# 2_classyTKL_MXHS_matrix.net
KiCad netlist of a schematic drawn in Altium Designer
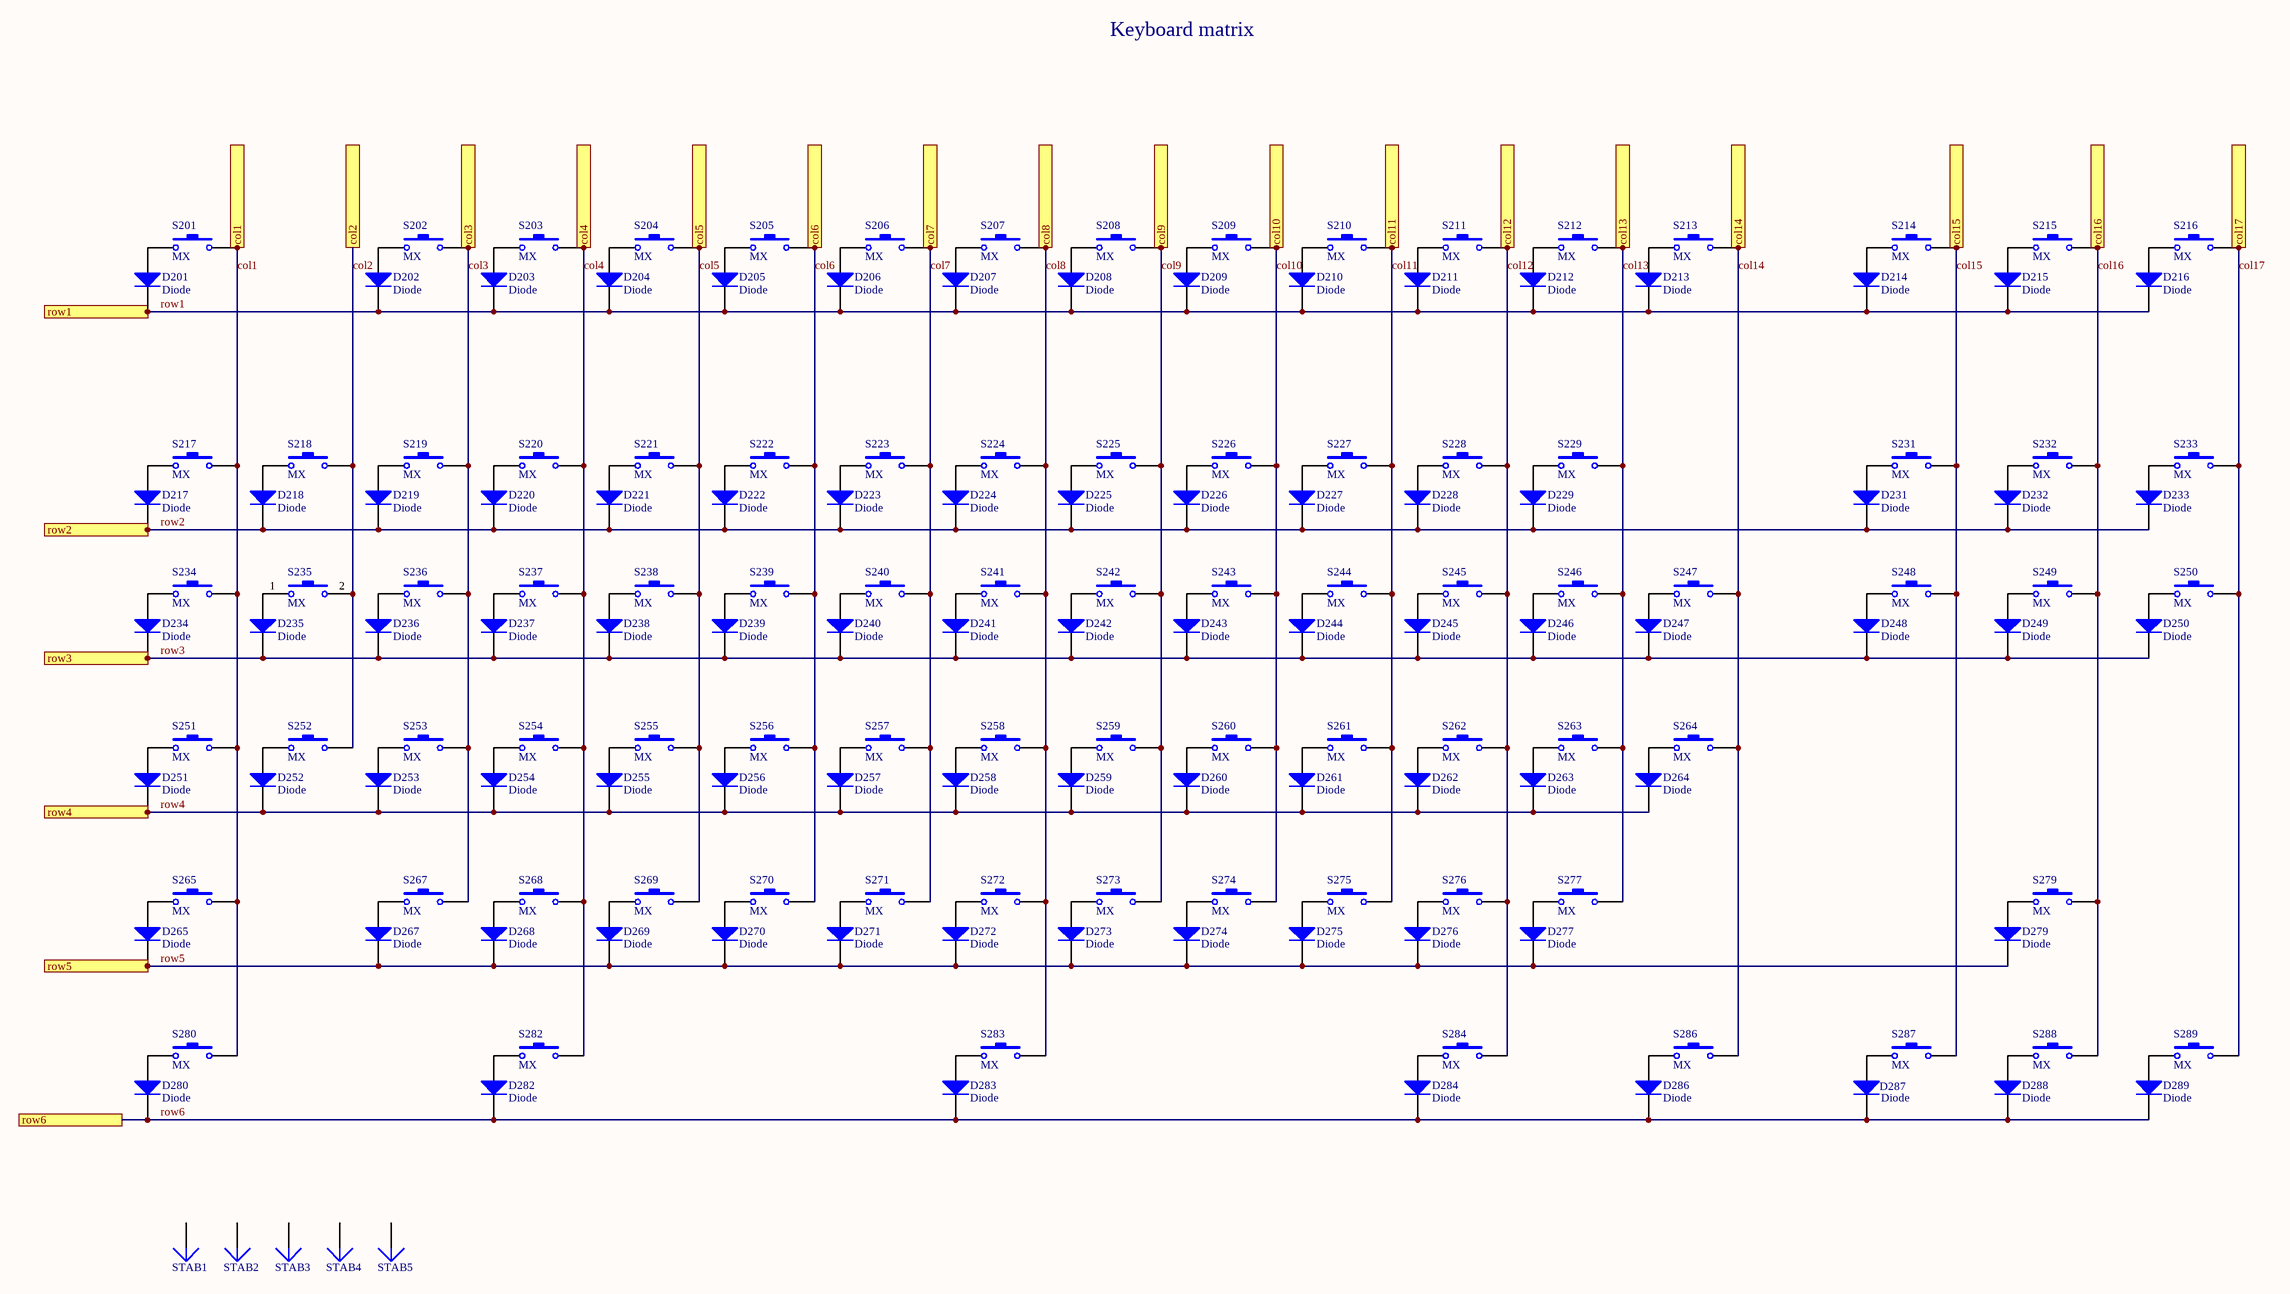
[diagram p0: 2_classyTKL_MXHS_matrix.SchDoc]

(export (version "E")
  (design (tool "Eeschema 10.0.6"))
  (components
    (comp (ref "D201")
      (value "Diode")
      (footprint "SOD-123")
      (description "Default Diode")
      (fields (field (name "LCSC PART #") "C81598") (field (name "MRF.PART") "1N4148W"))
      (libsource (lib "Miscellaneous Devices") (part "Diode"))
    )
    (comp (ref "D202")
      (value "Diode")
      (footprint "SOD-123")
      (description "Default Diode")
      (fields (field (name "LCSC PART #") "C81598") (field (name "MRF.PART") "1N4148W"))
      (libsource (lib "Miscellaneous Devices") (part "Diode"))
    )
    (comp (ref "D203")
      (value "Diode")
      (footprint "SOD-123")
      (description "Default Diode")
      (fields (field (name "LCSC PART #") "C81598") (field (name "MRF.PART") "1N4148W"))
      (libsource (lib "Miscellaneous Devices") (part "Diode"))
    )
    (comp (ref "D204")
      (value "Diode")
      (footprint "SOD-123")
      (description "Default Diode")
      (fields (field (name "LCSC PART #") "C81598") (field (name "MRF.PART") "1N4148W"))
      (libsource (lib "Miscellaneous Devices") (part "Diode"))
    )
    (comp (ref "D205")
      (value "Diode")
      (footprint "SOD-123")
      (description "Default Diode")
      (fields (field (name "LCSC PART #") "C81598") (field (name "MRF.PART") "1N4148W"))
      (libsource (lib "Miscellaneous Devices") (part "Diode"))
    )
    (comp (ref "D206")
      (value "Diode")
      (footprint "SOD-123")
      (description "Default Diode")
      (fields (field (name "LCSC PART #") "C81598") (field (name "MRF.PART") "1N4148W"))
      (libsource (lib "Miscellaneous Devices") (part "Diode"))
    )
    (comp (ref "D207")
      (value "Diode")
      (footprint "SOD-123")
      (description "Default Diode")
      (fields (field (name "LCSC PART #") "C81598") (field (name "MRF.PART") "1N4148W"))
      (libsource (lib "Miscellaneous Devices") (part "Diode"))
    )
    (comp (ref "D208")
      (value "Diode")
      (footprint "SOD-123")
      (description "Default Diode")
      (fields (field (name "LCSC PART #") "C81598") (field (name "MRF.PART") "1N4148W"))
      (libsource (lib "Miscellaneous Devices") (part "Diode"))
    )
    (comp (ref "D209")
      (value "Diode")
      (footprint "SOD-123")
      (description "Default Diode")
      (fields (field (name "LCSC PART #") "C81598") (field (name "MRF.PART") "1N4148W"))
      (libsource (lib "Miscellaneous Devices") (part "Diode"))
    )
    (comp (ref "D210")
      (value "Diode")
      (footprint "SOD-123")
      (description "Default Diode")
      (fields (field (name "LCSC PART #") "C81598") (field (name "MRF.PART") "1N4148W"))
      (libsource (lib "Miscellaneous Devices") (part "Diode"))
    )
    (comp (ref "D211")
      (value "Diode")
      (footprint "SOD-123")
      (description "Default Diode")
      (fields (field (name "LCSC PART #") "C81598") (field (name "MRF.PART") "1N4148W"))
      (libsource (lib "Miscellaneous Devices") (part "Diode"))
    )
    (comp (ref "D212")
      (value "Diode")
      (footprint "SOD-123")
      (description "Default Diode")
      (fields (field (name "LCSC PART #") "C81598") (field (name "MRF.PART") "1N4148W"))
      (libsource (lib "Miscellaneous Devices") (part "Diode"))
    )
    (comp (ref "D213")
      (value "Diode")
      (footprint "SOD-123")
      (description "Default Diode")
      (fields (field (name "LCSC PART #") "C81598") (field (name "MRF.PART") "1N4148W"))
      (libsource (lib "Miscellaneous Devices") (part "Diode"))
    )
    (comp (ref "D214")
      (value "Diode")
      (footprint "SOD-123")
      (description "Default Diode")
      (fields (field (name "LCSC PART #") "C81598") (field (name "MRF.PART") "1N4148W"))
      (libsource (lib "Miscellaneous Devices") (part "Diode"))
    )
    (comp (ref "D215")
      (value "Diode")
      (footprint "SOD-123")
      (description "Default Diode")
      (fields (field (name "LCSC PART #") "C81598") (field (name "MRF.PART") "1N4148W"))
      (libsource (lib "Miscellaneous Devices") (part "Diode"))
    )
    (comp (ref "D216")
      (value "Diode")
      (footprint "SOD-123")
      (description "Default Diode")
      (fields (field (name "LCSC PART #") "C81598") (field (name "MRF.PART") "1N4148W"))
      (libsource (lib "Miscellaneous Devices") (part "Diode"))
    )
    (comp (ref "D217")
      (value "Diode")
      (footprint "SOD-123")
      (description "Default Diode")
      (fields (field (name "LCSC PART #") "C81598") (field (name "MRF.PART") "1N4148W"))
      (libsource (lib "Miscellaneous Devices") (part "Diode"))
    )
    (comp (ref "D218")
      (value "Diode")
      (footprint "SOD-123")
      (description "Default Diode")
      (fields (field (name "LCSC PART #") "C81598") (field (name "MRF.PART") "1N4148W"))
      (libsource (lib "Miscellaneous Devices") (part "Diode"))
    )
    (comp (ref "D219")
      (value "Diode")
      (footprint "SOD-123")
      (description "Default Diode")
      (fields (field (name "LCSC PART #") "C81598") (field (name "MRF.PART") "1N4148W"))
      (libsource (lib "Miscellaneous Devices") (part "Diode"))
    )
    (comp (ref "D220")
      (value "Diode")
      (footprint "SOD-123")
      (description "Default Diode")
      (fields (field (name "LCSC PART #") "C81598") (field (name "MRF.PART") "1N4148W"))
      (libsource (lib "Miscellaneous Devices") (part "Diode"))
    )
    (comp (ref "D221")
      (value "Diode")
      (footprint "SOD-123")
      (description "Default Diode")
      (fields (field (name "LCSC PART #") "C81598") (field (name "MRF.PART") "1N4148W"))
      (libsource (lib "Miscellaneous Devices") (part "Diode"))
    )
    (comp (ref "D222")
      (value "Diode")
      (footprint "SOD-123")
      (description "Default Diode")
      (fields (field (name "LCSC PART #") "C81598") (field (name "MRF.PART") "1N4148W"))
      (libsource (lib "Miscellaneous Devices") (part "Diode"))
    )
    (comp (ref "D223")
      (value "Diode")
      (footprint "SOD-123")
      (description "Default Diode")
      (fields (field (name "LCSC PART #") "C81598") (field (name "MRF.PART") "1N4148W"))
      (libsource (lib "Miscellaneous Devices") (part "Diode"))
    )
    (comp (ref "D224")
      (value "Diode")
      (footprint "SOD-123")
      (description "Default Diode")
      (fields (field (name "LCSC PART #") "C81598") (field (name "MRF.PART") "1N4148W"))
      (libsource (lib "Miscellaneous Devices") (part "Diode"))
    )
    (comp (ref "D225")
      (value "Diode")
      (footprint "SOD-123")
      (description "Default Diode")
      (fields (field (name "LCSC PART #") "C81598") (field (name "MRF.PART") "1N4148W"))
      (libsource (lib "Miscellaneous Devices") (part "Diode"))
    )
    (comp (ref "D226")
      (value "Diode")
      (footprint "SOD-123")
      (description "Default Diode")
      (fields (field (name "LCSC PART #") "C81598") (field (name "MRF.PART") "1N4148W"))
      (libsource (lib "Miscellaneous Devices") (part "Diode"))
    )
    (comp (ref "D227")
      (value "Diode")
      (footprint "SOD-123")
      (description "Default Diode")
      (fields (field (name "LCSC PART #") "C81598") (field (name "MRF.PART") "1N4148W"))
      (libsource (lib "Miscellaneous Devices") (part "Diode"))
    )
    (comp (ref "D228")
      (value "Diode")
      (footprint "SOD-123")
      (description "Default Diode")
      (fields (field (name "LCSC PART #") "C81598") (field (name "MRF.PART") "1N4148W"))
      (libsource (lib "Miscellaneous Devices") (part "Diode"))
    )
    (comp (ref "D229")
      (value "Diode")
      (footprint "SOD-123")
      (description "Default Diode")
      (fields (field (name "LCSC PART #") "C81598") (field (name "MRF.PART") "1N4148W"))
      (libsource (lib "Miscellaneous Devices") (part "Diode"))
    )
    (comp (ref "D231")
      (value "Diode")
      (footprint "SOD-123")
      (description "Default Diode")
      (fields (field (name "LCSC PART #") "C81598") (field (name "MRF.PART") "1N4148W"))
      (libsource (lib "Miscellaneous Devices") (part "Diode"))
    )
    (comp (ref "D232")
      (value "Diode")
      (footprint "SOD-123")
      (description "Default Diode")
      (fields (field (name "LCSC PART #") "C81598") (field (name "MRF.PART") "1N4148W"))
      (libsource (lib "Miscellaneous Devices") (part "Diode"))
    )
    (comp (ref "D233")
      (value "Diode")
      (footprint "SOD-123")
      (description "Default Diode")
      (fields (field (name "LCSC PART #") "C81598") (field (name "MRF.PART") "1N4148W"))
      (libsource (lib "Miscellaneous Devices") (part "Diode"))
    )
    (comp (ref "D234")
      (value "Diode")
      (footprint "SOD-123")
      (description "Default Diode")
      (fields (field (name "LCSC PART #") "C81598") (field (name "MRF.PART") "1N4148W"))
      (libsource (lib "Miscellaneous Devices") (part "Diode"))
    )
    (comp (ref "D235")
      (value "Diode")
      (footprint "SOD-123")
      (description "Default Diode")
      (fields (field (name "LCSC PART #") "C81598") (field (name "MRF.PART") "1N4148W"))
      (libsource (lib "Miscellaneous Devices") (part "Diode"))
    )
    (comp (ref "D236")
      (value "Diode")
      (footprint "SOD-123")
      (description "Default Diode")
      (fields (field (name "LCSC PART #") "C81598") (field (name "MRF.PART") "1N4148W"))
      (libsource (lib "Miscellaneous Devices") (part "Diode"))
    )
    (comp (ref "D237")
      (value "Diode")
      (footprint "SOD-123")
      (description "Default Diode")
      (fields (field (name "LCSC PART #") "C81598") (field (name "MRF.PART") "1N4148W"))
      (libsource (lib "Miscellaneous Devices") (part "Diode"))
    )
    (comp (ref "D238")
      (value "Diode")
      (footprint "SOD-123")
      (description "Default Diode")
      (fields (field (name "LCSC PART #") "C81598") (field (name "MRF.PART") "1N4148W"))
      (libsource (lib "Miscellaneous Devices") (part "Diode"))
    )
    (comp (ref "D239")
      (value "Diode")
      (footprint "SOD-123")
      (description "Default Diode")
      (fields (field (name "LCSC PART #") "C81598") (field (name "MRF.PART") "1N4148W"))
      (libsource (lib "Miscellaneous Devices") (part "Diode"))
    )
    (comp (ref "D240")
      (value "Diode")
      (footprint "SOD-123")
      (description "Default Diode")
      (fields (field (name "LCSC PART #") "C81598") (field (name "MRF.PART") "1N4148W"))
      (libsource (lib "Miscellaneous Devices") (part "Diode"))
    )
    (comp (ref "D241")
      (value "Diode")
      (footprint "SOD-123")
      (description "Default Diode")
      (fields (field (name "LCSC PART #") "C81598") (field (name "MRF.PART") "1N4148W"))
      (libsource (lib "Miscellaneous Devices") (part "Diode"))
    )
    (comp (ref "D242")
      (value "Diode")
      (footprint "SOD-123")
      (description "Default Diode")
      (fields (field (name "LCSC PART #") "C81598") (field (name "MRF.PART") "1N4148W"))
      (libsource (lib "Miscellaneous Devices") (part "Diode"))
    )
    (comp (ref "D243")
      (value "Diode")
      (footprint "SOD-123")
      (description "Default Diode")
      (fields (field (name "LCSC PART #") "C81598") (field (name "MRF.PART") "1N4148W"))
      (libsource (lib "Miscellaneous Devices") (part "Diode"))
    )
    (comp (ref "D244")
      (value "Diode")
      (footprint "SOD-123")
      (description "Default Diode")
      (fields (field (name "LCSC PART #") "C81598") (field (name "MRF.PART") "1N4148W"))
      (libsource (lib "Miscellaneous Devices") (part "Diode"))
    )
    (comp (ref "D245")
      (value "Diode")
      (footprint "SOD-123")
      (description "Default Diode")
      (fields (field (name "LCSC PART #") "C81598") (field (name "MRF.PART") "1N4148W"))
      (libsource (lib "Miscellaneous Devices") (part "Diode"))
    )
    (comp (ref "D246")
      (value "Diode")
      (footprint "SOD-123")
      (description "Default Diode")
      (fields (field (name "LCSC PART #") "C81598") (field (name "MRF.PART") "1N4148W"))
      (libsource (lib "Miscellaneous Devices") (part "Diode"))
    )
    (comp (ref "D247")
      (value "Diode")
      (footprint "SOD-123")
      (description "Default Diode")
      (fields (field (name "LCSC PART #") "C81598") (field (name "MRF.PART") "1N4148W"))
      (libsource (lib "Miscellaneous Devices") (part "Diode"))
    )
    (comp (ref "D248")
      (value "Diode")
      (footprint "SOD-123")
      (description "Default Diode")
      (fields (field (name "LCSC PART #") "C81598") (field (name "MRF.PART") "1N4148W"))
      (libsource (lib "Miscellaneous Devices") (part "Diode"))
    )
    (comp (ref "D249")
      (value "Diode")
      (footprint "SOD-123")
      (description "Default Diode")
      (fields (field (name "LCSC PART #") "C81598") (field (name "MRF.PART") "1N4148W"))
      (libsource (lib "Miscellaneous Devices") (part "Diode"))
    )
    (comp (ref "D250")
      (value "Diode")
      (footprint "SOD-123")
      (description "Default Diode")
      (fields (field (name "LCSC PART #") "C81598") (field (name "MRF.PART") "1N4148W"))
      (libsource (lib "Miscellaneous Devices") (part "Diode"))
    )
    (comp (ref "D251")
      (value "Diode")
      (footprint "SOD-123")
      (description "Default Diode")
      (fields (field (name "LCSC PART #") "C81598") (field (name "MRF.PART") "1N4148W"))
      (libsource (lib "Miscellaneous Devices") (part "Diode"))
    )
    (comp (ref "D252")
      (value "Diode")
      (footprint "SOD-123")
      (description "Default Diode")
      (fields (field (name "LCSC PART #") "C81598") (field (name "MRF.PART") "1N4148W"))
      (libsource (lib "Miscellaneous Devices") (part "Diode"))
    )
    (comp (ref "D253")
      (value "Diode")
      (footprint "SOD-123")
      (description "Default Diode")
      (fields (field (name "LCSC PART #") "C81598") (field (name "MRF.PART") "1N4148W"))
      (libsource (lib "Miscellaneous Devices") (part "Diode"))
    )
    (comp (ref "D254")
      (value "Diode")
      (footprint "SOD-123")
      (description "Default Diode")
      (fields (field (name "LCSC PART #") "C81598") (field (name "MRF.PART") "1N4148W"))
      (libsource (lib "Miscellaneous Devices") (part "Diode"))
    )
    (comp (ref "D255")
      (value "Diode")
      (footprint "SOD-123")
      (description "Default Diode")
      (fields (field (name "LCSC PART #") "C81598") (field (name "MRF.PART") "1N4148W"))
      (libsource (lib "Miscellaneous Devices") (part "Diode"))
    )
    (comp (ref "D256")
      (value "Diode")
      (footprint "SOD-123")
      (description "Default Diode")
      (fields (field (name "LCSC PART #") "C81598") (field (name "MRF.PART") "1N4148W"))
      (libsource (lib "Miscellaneous Devices") (part "Diode"))
    )
    (comp (ref "D257")
      (value "Diode")
      (footprint "SOD-123")
      (description "Default Diode")
      (fields (field (name "LCSC PART #") "C81598") (field (name "MRF.PART") "1N4148W"))
      (libsource (lib "Miscellaneous Devices") (part "Diode"))
    )
    (comp (ref "D258")
      (value "Diode")
      (footprint "SOD-123")
      (description "Default Diode")
      (fields (field (name "LCSC PART #") "C81598") (field (name "MRF.PART") "1N4148W"))
      (libsource (lib "Miscellaneous Devices") (part "Diode"))
    )
    (comp (ref "D259")
      (value "Diode")
      (footprint "SOD-123")
      (description "Default Diode")
      (fields (field (name "LCSC PART #") "C81598") (field (name "MRF.PART") "1N4148W"))
      (libsource (lib "Miscellaneous Devices") (part "Diode"))
    )
    (comp (ref "D260")
      (value "Diode")
      (footprint "SOD-123")
      (description "Default Diode")
      (fields (field (name "LCSC PART #") "C81598") (field (name "MRF.PART") "1N4148W"))
      (libsource (lib "Miscellaneous Devices") (part "Diode"))
    )
    (comp (ref "D261")
      (value "Diode")
      (footprint "SOD-123")
      (description "Default Diode")
      (fields (field (name "LCSC PART #") "C81598") (field (name "MRF.PART") "1N4148W"))
      (libsource (lib "Miscellaneous Devices") (part "Diode"))
    )
    (comp (ref "D262")
      (value "Diode")
      (footprint "SOD-123")
      (description "Default Diode")
      (fields (field (name "LCSC PART #") "C81598") (field (name "MRF.PART") "1N4148W"))
      (libsource (lib "Miscellaneous Devices") (part "Diode"))
    )
    (comp (ref "D263")
      (value "Diode")
      (footprint "SOD-123")
      (description "Default Diode")
      (fields (field (name "LCSC PART #") "C81598") (field (name "MRF.PART") "1N4148W"))
      (libsource (lib "Miscellaneous Devices") (part "Diode"))
    )
    (comp (ref "D264")
      (value "Diode")
      (footprint "SOD-123")
      (description "Default Diode")
      (fields (field (name "LCSC PART #") "C81598") (field (name "MRF.PART") "1N4148W"))
      (libsource (lib "Miscellaneous Devices") (part "Diode"))
    )
    (comp (ref "D265")
      (value "Diode")
      (footprint "SOD-123")
      (description "Default Diode")
      (fields (field (name "LCSC PART #") "C81598") (field (name "MRF.PART") "1N4148W"))
      (libsource (lib "Miscellaneous Devices") (part "Diode"))
    )
    (comp (ref "D267")
      (value "Diode")
      (footprint "SOD-123")
      (description "Default Diode")
      (fields (field (name "LCSC PART #") "C81598") (field (name "MRF.PART") "1N4148W"))
      (libsource (lib "Miscellaneous Devices") (part "Diode"))
    )
    (comp (ref "D268")
      (value "Diode")
      (footprint "SOD-123")
      (description "Default Diode")
      (fields (field (name "LCSC PART #") "C81598") (field (name "MRF.PART") "1N4148W"))
      (libsource (lib "Miscellaneous Devices") (part "Diode"))
    )
    (comp (ref "D269")
      (value "Diode")
      (footprint "SOD-123")
      (description "Default Diode")
      (fields (field (name "LCSC PART #") "C81598") (field (name "MRF.PART") "1N4148W"))
      (libsource (lib "Miscellaneous Devices") (part "Diode"))
    )
    (comp (ref "D270")
      (value "Diode")
      (footprint "SOD-123")
      (description "Default Diode")
      (fields (field (name "LCSC PART #") "C81598") (field (name "MRF.PART") "1N4148W"))
      (libsource (lib "Miscellaneous Devices") (part "Diode"))
    )
    (comp (ref "D271")
      (value "Diode")
      (footprint "SOD-123")
      (description "Default Diode")
      (fields (field (name "LCSC PART #") "C81598") (field (name "MRF.PART") "1N4148W"))
      (libsource (lib "Miscellaneous Devices") (part "Diode"))
    )
    (comp (ref "D272")
      (value "Diode")
      (footprint "SOD-123")
      (description "Default Diode")
      (fields (field (name "LCSC PART #") "C81598") (field (name "MRF.PART") "1N4148W"))
      (libsource (lib "Miscellaneous Devices") (part "Diode"))
    )
    (comp (ref "D273")
      (value "Diode")
      (footprint "SOD-123")
      (description "Default Diode")
      (fields (field (name "LCSC PART #") "C81598") (field (name "MRF.PART") "1N4148W"))
      (libsource (lib "Miscellaneous Devices") (part "Diode"))
    )
    (comp (ref "D274")
      (value "Diode")
      (footprint "SOD-123")
      (description "Default Diode")
      (fields (field (name "LCSC PART #") "C81598") (field (name "MRF.PART") "1N4148W"))
      (libsource (lib "Miscellaneous Devices") (part "Diode"))
    )
    (comp (ref "D275")
      (value "Diode")
      (footprint "SOD-123")
      (description "Default Diode")
      (fields (field (name "LCSC PART #") "C81598") (field (name "MRF.PART") "1N4148W"))
      (libsource (lib "Miscellaneous Devices") (part "Diode"))
    )
    (comp (ref "D276")
      (value "Diode")
      (footprint "SOD-123")
      (description "Default Diode")
      (fields (field (name "LCSC PART #") "C81598") (field (name "MRF.PART") "1N4148W"))
      (libsource (lib "Miscellaneous Devices") (part "Diode"))
    )
    (comp (ref "D277")
      (value "Diode")
      (footprint "SOD-123")
      (description "Default Diode")
      (fields (field (name "LCSC PART #") "C81598") (field (name "MRF.PART") "1N4148W"))
      (libsource (lib "Miscellaneous Devices") (part "Diode"))
    )
    (comp (ref "D279")
      (value "Diode")
      (footprint "SOD-123")
      (description "Default Diode")
      (fields (field (name "LCSC PART #") "C81598") (field (name "MRF.PART") "1N4148W"))
      (libsource (lib "Miscellaneous Devices") (part "Diode"))
    )
    (comp (ref "D280")
      (value "Diode")
      (footprint "SOD-123")
      (description "Default Diode")
      (fields (field (name "LCSC PART #") "C81598") (field (name "MRF.PART") "1N4148W"))
      (libsource (lib "Miscellaneous Devices") (part "Diode"))
    )
    (comp (ref "D282")
      (value "Diode")
      (footprint "SOD-123")
      (description "Default Diode")
      (fields (field (name "LCSC PART #") "C81598") (field (name "MRF.PART") "1N4148W"))
      (libsource (lib "Miscellaneous Devices") (part "Diode"))
    )
    (comp (ref "D283")
      (value "Diode")
      (footprint "SOD-123")
      (description "Default Diode")
      (fields (field (name "LCSC PART #") "C81598") (field (name "MRF.PART") "1N4148W"))
      (libsource (lib "Miscellaneous Devices") (part "Diode"))
    )
    (comp (ref "D284")
      (value "Diode")
      (footprint "SOD-123")
      (description "Default Diode")
      (fields (field (name "LCSC PART #") "C81598") (field (name "MRF.PART") "1N4148W"))
      (libsource (lib "Miscellaneous Devices") (part "Diode"))
    )
    (comp (ref "D286")
      (value "Diode")
      (footprint "SOD-123")
      (description "Default Diode")
      (fields (field (name "LCSC PART #") "C81598") (field (name "MRF.PART") "1N4148W"))
      (libsource (lib "Miscellaneous Devices") (part "Diode"))
    )
    (comp (ref "D287")
      (value "Diode")
      (footprint "SOD-123")
      (description "Default Diode")
      (fields (field (name "LCSC PART #") "C81598") (field (name "MRF.PART") "1N4148W"))
      (libsource (lib "Miscellaneous Devices") (part "Diode"))
    )
    (comp (ref "D288")
      (value "Diode")
      (footprint "SOD-123")
      (description "Default Diode")
      (fields (field (name "LCSC PART #") "C81598") (field (name "MRF.PART") "1N4148W"))
      (libsource (lib "Miscellaneous Devices") (part "Diode"))
    )
    (comp (ref "D289")
      (value "Diode")
      (footprint "SOD-123")
      (description "Default Diode")
      (fields (field (name "LCSC PART #") "C81598") (field (name "MRF.PART") "1N4148W"))
      (libsource (lib "Miscellaneous Devices") (part "Diode"))
    )
    (comp (ref "S201")
      (value "MX")
      (footprint "MXHS-switch")
      (description "Switch")
      (libsource (lib "Miscellaneous Devices") (part "SW-PB"))
    )
    (comp (ref "S202")
      (value "MX")
      (footprint "MXHS-switch_Switched_Pol")
      (description "Switch")
      (libsource (lib "Miscellaneous Devices") (part "SW-PB"))
    )
    (comp (ref "S203")
      (value "MX")
      (footprint "MXHS-switch_Switched_Pol")
      (description "Switch")
      (libsource (lib "Miscellaneous Devices") (part "SW-PB"))
    )
    (comp (ref "S204")
      (value "MX")
      (footprint "MXHS-switch_Switched_Pol")
      (description "Switch")
      (libsource (lib "Miscellaneous Devices") (part "SW-PB"))
    )
    (comp (ref "S205")
      (value "MX")
      (footprint "MXHS-switch")
      (description "Switch")
      (libsource (lib "Miscellaneous Devices") (part "SW-PB"))
    )
    (comp (ref "S206")
      (value "MX")
      (footprint "MXHS-switch_Switched_Pol")
      (description "Switch")
      (libsource (lib "Miscellaneous Devices") (part "SW-PB"))
    )
    (comp (ref "S207")
      (value "MX")
      (footprint "MXHS-switch_Switched_Pol")
      (description "Switch")
      (libsource (lib "Miscellaneous Devices") (part "SW-PB"))
    )
    (comp (ref "S208")
      (value "MX")
      (footprint "MXHS-switch_Switched_Pol")
      (description "Switch")
      (libsource (lib "Miscellaneous Devices") (part "SW-PB"))
    )
    (comp (ref "S209")
      (value "MX")
      (footprint "MXHS-switch_Switched_Pol")
      (description "Switch")
      (libsource (lib "Miscellaneous Devices") (part "SW-PB"))
    )
    (comp (ref "S210")
      (value "MX")
      (footprint "MXHS-switch_Switched_Pol")
      (description "Switch")
      (libsource (lib "Miscellaneous Devices") (part "SW-PB"))
    )
    (comp (ref "S211")
      (value "MX")
      (footprint "MXHS-switch_Switched_Pol")
      (description "Switch")
      (libsource (lib "Miscellaneous Devices") (part "SW-PB"))
    )
    (comp (ref "S212")
      (value "MX")
      (footprint "MXHS-switch_Switched_Pol")
      (description "Switch")
      (libsource (lib "Miscellaneous Devices") (part "SW-PB"))
    )
    (comp (ref "S213")
      (value "MX")
      (footprint "MXHS-switch_Switched_Pol")
      (description "Switch")
      (libsource (lib "Miscellaneous Devices") (part "SW-PB"))
    )
    (comp (ref "S214")
      (value "MX")
      (footprint "MXHS-switch_Switched_Pol")
      (description "Switch")
      (libsource (lib "Miscellaneous Devices") (part "SW-PB"))
    )
    (comp (ref "S215")
      (value "MX")
      (footprint "MXHS-switch_Switched_Pol")
      (description "Switch")
      (libsource (lib "Miscellaneous Devices") (part "SW-PB"))
    )
    (comp (ref "S216")
      (value "MX")
      (footprint "MXHS-switch_Switched_Pol")
      (description "Switch")
      (libsource (lib "Miscellaneous Devices") (part "SW-PB"))
    )
    (comp (ref "S217")
      (value "MX")
      (footprint "MXHS-switch")
      (description "Switch")
      (libsource (lib "Miscellaneous Devices") (part "SW-PB"))
    )
    (comp (ref "S218")
      (value "MX")
      (footprint "MXHS-switch")
      (description "Switch")
      (libsource (lib "Miscellaneous Devices") (part "SW-PB"))
    )
    (comp (ref "S219")
      (value "MX")
      (footprint "MXHS-switch")
      (description "Switch")
      (libsource (lib "Miscellaneous Devices") (part "SW-PB"))
    )
    (comp (ref "S220")
      (value "MX")
      (footprint "MXHS-switch")
      (description "Switch")
      (libsource (lib "Miscellaneous Devices") (part "SW-PB"))
    )
    (comp (ref "S221")
      (value "MX")
      (footprint "MXHS-switch")
      (description "Switch")
      (libsource (lib "Miscellaneous Devices") (part "SW-PB"))
    )
    (comp (ref "S222")
      (value "MX")
      (footprint "MXHS-switch")
      (description "Switch")
      (libsource (lib "Miscellaneous Devices") (part "SW-PB"))
    )
    (comp (ref "S223")
      (value "MX")
      (footprint "MXHS-switch")
      (description "Switch")
      (libsource (lib "Miscellaneous Devices") (part "SW-PB"))
    )
    (comp (ref "S224")
      (value "MX")
      (footprint "MXHS-switch")
      (description "Switch")
      (libsource (lib "Miscellaneous Devices") (part "SW-PB"))
    )
    (comp (ref "S225")
      (value "MX")
      (footprint "MXHS-switch")
      (description "Switch")
      (libsource (lib "Miscellaneous Devices") (part "SW-PB"))
    )
    (comp (ref "S226")
      (value "MX")
      (footprint "MXHS-switch")
      (description "Switch")
      (libsource (lib "Miscellaneous Devices") (part "SW-PB"))
    )
    (comp (ref "S227")
      (value "MX")
      (footprint "MXHS-switch")
      (description "Switch")
      (libsource (lib "Miscellaneous Devices") (part "SW-PB"))
    )
    (comp (ref "S228")
      (value "MX")
      (footprint "MXHS-switch")
      (description "Switch")
      (libsource (lib "Miscellaneous Devices") (part "SW-PB"))
    )
    (comp (ref "S229")
      (value "MX")
      (footprint "MXHS-switch")
      (description "Switch")
      (libsource (lib "Miscellaneous Devices") (part "SW-PB"))
    )
    (comp (ref "S231")
      (value "MX")
      (footprint "MXHS-switch_Switched_Pol")
      (description "Switch")
      (libsource (lib "Miscellaneous Devices") (part "SW-PB"))
    )
    (comp (ref "S232")
      (value "MX")
      (footprint "MXHS-switch_Switched_Pol")
      (description "Switch")
      (libsource (lib "Miscellaneous Devices") (part "SW-PB"))
    )
    (comp (ref "S233")
      (value "MX")
      (footprint "MXHS-switch_Switched_Pol")
      (description "Switch")
      (libsource (lib "Miscellaneous Devices") (part "SW-PB"))
    )
    (comp (ref "S234")
      (value "MX")
      (footprint "MXHS-switch - 1.5U")
      (description "TAB")
      (libsource (lib "Miscellaneous Devices") (part "SW-PB"))
    )
    (comp (ref "S235")
      (value "MX")
      (footprint "MXHS-switch")
      (description "Switch")
      (libsource (lib "") (part "SW-PB_1"))
    )
    (comp (ref "S236")
      (value "MX")
      (footprint "MXHS-switch")
      (description "Switch")
      (libsource (lib "Miscellaneous Devices") (part "SW-PB"))
    )
    (comp (ref "S237")
      (value "MX")
      (footprint "MXHS-switch")
      (description "Switch")
      (libsource (lib "Miscellaneous Devices") (part "SW-PB"))
    )
    (comp (ref "S238")
      (value "MX")
      (footprint "MXHS-switch")
      (description "Switch")
      (libsource (lib "Miscellaneous Devices") (part "SW-PB"))
    )
    (comp (ref "S239")
      (value "MX")
      (footprint "MXHS-switch")
      (description "Switch")
      (libsource (lib "Miscellaneous Devices") (part "SW-PB"))
    )
    (comp (ref "S240")
      (value "MX")
      (footprint "MXHS-switch")
      (description "Switch")
      (libsource (lib "Miscellaneous Devices") (part "SW-PB"))
    )
    (comp (ref "S241")
      (value "MX")
      (footprint "MXHS-switch")
      (description "Switch")
      (libsource (lib "Miscellaneous Devices") (part "SW-PB"))
    )
    (comp (ref "S242")
      (value "MX")
      (footprint "MXHS-switch")
      (description "Switch")
      (libsource (lib "Miscellaneous Devices") (part "SW-PB"))
    )
    (comp (ref "S243")
      (value "MX")
      (footprint "MXHS-switch")
      (description "Switch")
      (libsource (lib "Miscellaneous Devices") (part "SW-PB"))
    )
    (comp (ref "S244")
      (value "MX")
      (footprint "MXHS-switch")
      (description "Switch")
      (libsource (lib "Miscellaneous Devices") (part "SW-PB"))
    )
    (comp (ref "S245")
      (value "MX")
      (footprint "MXHS-switch")
      (description "Switch")
      (libsource (lib "Miscellaneous Devices") (part "SW-PB"))
    )
    (comp (ref "S246")
      (value "MX")
      (footprint "MXHS-switch")
      (description "Switch")
      (libsource (lib "Miscellaneous Devices") (part "SW-PB"))
    )
    (comp (ref "S247")
      (value "MX")
      (footprint "MXHS-switch_Switched_Pol")
      (description "Switch")
      (libsource (lib "Miscellaneous Devices") (part "SW-PB"))
    )
    (comp (ref "S248")
      (value "MX")
      (footprint "MXHS-switch_Switched_Pol")
      (description "Switch")
      (libsource (lib "Miscellaneous Devices") (part "SW-PB"))
    )
    (comp (ref "S249")
      (value "MX")
      (footprint "MXHS-switch_Switched_Pol")
      (description "Switch")
      (libsource (lib "Miscellaneous Devices") (part "SW-PB"))
    )
    (comp (ref "S250")
      (value "MX")
      (footprint "MXHS-switch_Switched_Pol")
      (description "Switch")
      (libsource (lib "Miscellaneous Devices") (part "SW-PB"))
    )
    (comp (ref "S251")
      (value "MX")
      (footprint "MXHS-switch")
      (description "Switch")
      (libsource (lib "Miscellaneous Devices") (part "SW-PB"))
    )
    (comp (ref "S252")
      (value "MX")
      (footprint "MXHS-switch")
      (description "Switch")
      (libsource (lib "Miscellaneous Devices") (part "SW-PB"))
    )
    (comp (ref "S253")
      (value "MX")
      (footprint "MXHS-switch")
      (description "Switch")
      (libsource (lib "Miscellaneous Devices") (part "SW-PB"))
    )
    (comp (ref "S254")
      (value "MX")
      (footprint "MXHS-switch")
      (description "Switch")
      (libsource (lib "Miscellaneous Devices") (part "SW-PB"))
    )
    (comp (ref "S255")
      (value "MX")
      (footprint "MXHS-switch")
      (description "Switch")
      (libsource (lib "Miscellaneous Devices") (part "SW-PB"))
    )
    (comp (ref "S256")
      (value "MX")
      (footprint "MXHS-switch")
      (description "Switch")
      (libsource (lib "Miscellaneous Devices") (part "SW-PB"))
    )
    (comp (ref "S257")
      (value "MX")
      (footprint "MXHS-switch")
      (description "Switch")
      (libsource (lib "Miscellaneous Devices") (part "SW-PB"))
    )
    (comp (ref "S258")
      (value "MX")
      (footprint "MXHS-switch")
      (description "Switch")
      (libsource (lib "Miscellaneous Devices") (part "SW-PB"))
    )
    (comp (ref "S259")
      (value "MX")
      (footprint "MXHS-switch")
      (description "Switch")
      (libsource (lib "Miscellaneous Devices") (part "SW-PB"))
    )
    (comp (ref "S260")
      (value "MX")
      (footprint "MXHS-switch")
      (description "Switch")
      (libsource (lib "Miscellaneous Devices") (part "SW-PB"))
    )
    (comp (ref "S261")
      (value "MX")
      (footprint "MXHS-switch")
      (description "Switch")
      (libsource (lib "Miscellaneous Devices") (part "SW-PB"))
    )
    (comp (ref "S262")
      (value "MX")
      (footprint "MXHS-switch")
      (description "Switch")
      (libsource (lib "Miscellaneous Devices") (part "SW-PB"))
    )
    (comp (ref "S263")
      (value "MX")
      (footprint "MXHS-switch")
      (description "Switch")
      (libsource (lib "Miscellaneous Devices") (part "SW-PB"))
    )
    (comp (ref "S264")
      (value "MX")
      (footprint "MXHS-switch")
      (description "Switch")
      (libsource (lib "Miscellaneous Devices") (part "SW-PB"))
    )
    (comp (ref "S265")
      (value "MX")
      (footprint "MXHS-switch")
      (description "Switch")
      (libsource (lib "Miscellaneous Devices") (part "SW-PB"))
    )
    (comp (ref "S267")
      (value "MX")
      (footprint "MXHS-switch")
      (description "Switch")
      (libsource (lib "Miscellaneous Devices") (part "SW-PB"))
    )
    (comp (ref "S268")
      (value "MX")
      (footprint "MXHS-switch")
      (description "Switch")
      (libsource (lib "Miscellaneous Devices") (part "SW-PB"))
    )
    (comp (ref "S269")
      (value "MX")
      (footprint "MXHS-switch")
      (description "Switch")
      (libsource (lib "Miscellaneous Devices") (part "SW-PB"))
    )
    (comp (ref "S270")
      (value "MX")
      (footprint "MXHS-switch")
      (description "Switch")
      (libsource (lib "Miscellaneous Devices") (part "SW-PB"))
    )
    (comp (ref "S271")
      (value "MX")
      (footprint "MXHS-switch")
      (description "Switch")
      (libsource (lib "Miscellaneous Devices") (part "SW-PB"))
    )
    (comp (ref "S272")
      (value "MX")
      (footprint "MXHS-switch")
      (description "Switch")
      (libsource (lib "Miscellaneous Devices") (part "SW-PB"))
    )
    (comp (ref "S273")
      (value "MX")
      (footprint "MXHS-switch")
      (description "Switch")
      (libsource (lib "Miscellaneous Devices") (part "SW-PB"))
    )
    (comp (ref "S274")
      (value "MX")
      (footprint "MXHS-switch")
      (description "Switch")
      (libsource (lib "Miscellaneous Devices") (part "SW-PB"))
    )
    (comp (ref "S275")
      (value "MX")
      (footprint "MXHS-switch")
      (description "Switch")
      (libsource (lib "Miscellaneous Devices") (part "SW-PB"))
    )
    (comp (ref "S276")
      (value "MX")
      (footprint "MXHS-switch")
      (description "Switch")
      (libsource (lib "Miscellaneous Devices") (part "SW-PB"))
    )
    (comp (ref "S277")
      (value "MX")
      (footprint "MXHS-switch")
      (description "Switch")
      (libsource (lib "Miscellaneous Devices") (part "SW-PB"))
    )
    (comp (ref "S279")
      (value "MX")
      (footprint "MXHS-switch_Switched_Pol")
      (description "Switch")
      (libsource (lib "Miscellaneous Devices") (part "SW-PB"))
    )
    (comp (ref "S280")
      (value "MX")
      (footprint "MXHS-switch")
      (description "Switch")
      (libsource (lib "Miscellaneous Devices") (part "SW-PB"))
    )
    (comp (ref "S282")
      (value "MX")
      (footprint "MXHS-switch_Switched_Pol")
      (description "Switch")
      (libsource (lib "Miscellaneous Devices") (part "SW-PB"))
    )
    (comp (ref "S283")
      (value "MX")
      (footprint "MXHS-switch")
      (description "Switch")
      (libsource (lib "Miscellaneous Devices") (part "SW-PB"))
    )
    (comp (ref "S284")
      (value "MX")
      (footprint "MXHS-switch_Switched_Pol")
      (description "Switch")
      (libsource (lib "Miscellaneous Devices") (part "SW-PB"))
    )
    (comp (ref "S286")
      (value "MX")
      (footprint "MXHS-switch_Switched_Pol")
      (description "Switch")
      (libsource (lib "Miscellaneous Devices") (part "SW-PB"))
    )
    (comp (ref "S287")
      (value "MX")
      (footprint "MXHS-switch_Switched_Pol")
      (description "Switch")
      (libsource (lib "Miscellaneous Devices") (part "SW-PB"))
    )
    (comp (ref "S288")
      (value "MX")
      (footprint "MXHS-switch_Switched_Pol")
      (description "Switch")
      (libsource (lib "Miscellaneous Devices") (part "SW-PB"))
    )
    (comp (ref "S289")
      (value "MX")
      (footprint "MXHS-switch_Switched_Pol")
      (description "Switch")
      (libsource (lib "Miscellaneous Devices") (part "SW-PB"))
    )
    (comp (ref "STAB1")
      (value "Plug")
      (footprint "Stab 2u")
      (libsource (lib "Miscellaneous Connectors") (part "Plug"))
    )
    (comp (ref "STAB2")
      (value "Plug")
      (footprint "Stab 2u")
      (libsource (lib "Miscellaneous Connectors") (part "Plug"))
    )
    (comp (ref "STAB3")
      (value "Plug")
      (footprint "Stab 2u")
      (libsource (lib "Miscellaneous Connectors") (part "Plug"))
    )
    (comp (ref "STAB4")
      (value "Plug")
      (footprint "Stab 2u")
      (libsource (lib "Miscellaneous Connectors") (part "Plug"))
    )
    (comp (ref "STAB5")
      (value "Plug")
      (footprint "Stab 7U")
      (libsource (lib "Miscellaneous Connectors") (part "Plug"))
    )
  )
  (nets
    (net (code "1") (name "/col1") (class "Default")
      (node (ref "S201") (pin "2") (pinfunction "2_2") (pintype "passive"))
      (node (ref "S217") (pin "2") (pinfunction "2_2") (pintype "passive"))
      (node (ref "S234") (pin "2") (pinfunction "2_2") (pintype "passive"))
      (node (ref "S251") (pin "2") (pinfunction "2_2") (pintype "passive"))
      (node (ref "S265") (pin "2") (pinfunction "2_2") (pintype "passive"))
      (node (ref "S280") (pin "2") (pinfunction "2_2") (pintype "passive"))
    )
    (net (code "2") (name "/col2") (class "Default")
      (node (ref "S218") (pin "2") (pinfunction "2_2") (pintype "passive"))
      (node (ref "S235") (pin "2") (pinfunction "2_2") (pintype "passive"))
      (node (ref "S252") (pin "2") (pinfunction "2_2") (pintype "passive"))
    )
    (net (code "3") (name "/col3") (class "Default")
      (node (ref "S202") (pin "2") (pinfunction "2_2") (pintype "passive"))
      (node (ref "S219") (pin "2") (pinfunction "2_2") (pintype "passive"))
      (node (ref "S236") (pin "2") (pinfunction "2_2") (pintype "passive"))
      (node (ref "S253") (pin "2") (pinfunction "2_2") (pintype "passive"))
      (node (ref "S267") (pin "2") (pinfunction "2_2") (pintype "passive"))
    )
    (net (code "4") (name "/col4") (class "Default")
      (node (ref "S203") (pin "2") (pinfunction "2_2") (pintype "passive"))
      (node (ref "S220") (pin "2") (pinfunction "2_2") (pintype "passive"))
      (node (ref "S237") (pin "2") (pinfunction "2_2") (pintype "passive"))
      (node (ref "S254") (pin "2") (pinfunction "2_2") (pintype "passive"))
      (node (ref "S268") (pin "2") (pinfunction "2_2") (pintype "passive"))
      (node (ref "S282") (pin "2") (pinfunction "2_2") (pintype "passive"))
    )
    (net (code "5") (name "/col5") (class "Default")
      (node (ref "S204") (pin "2") (pinfunction "2_2") (pintype "passive"))
      (node (ref "S221") (pin "2") (pinfunction "2_2") (pintype "passive"))
      (node (ref "S238") (pin "2") (pinfunction "2_2") (pintype "passive"))
      (node (ref "S255") (pin "2") (pinfunction "2_2") (pintype "passive"))
      (node (ref "S269") (pin "2") (pinfunction "2_2") (pintype "passive"))
    )
    (net (code "6") (name "/col6") (class "Default")
      (node (ref "S205") (pin "2") (pinfunction "2_2") (pintype "passive"))
      (node (ref "S222") (pin "2") (pinfunction "2_2") (pintype "passive"))
      (node (ref "S239") (pin "2") (pinfunction "2_2") (pintype "passive"))
      (node (ref "S256") (pin "2") (pinfunction "2_2") (pintype "passive"))
      (node (ref "S270") (pin "2") (pinfunction "2_2") (pintype "passive"))
    )
    (net (code "7") (name "/col7") (class "Default")
      (node (ref "S206") (pin "2") (pinfunction "2_2") (pintype "passive"))
      (node (ref "S223") (pin "2") (pinfunction "2_2") (pintype "passive"))
      (node (ref "S240") (pin "2") (pinfunction "2_2") (pintype "passive"))
      (node (ref "S257") (pin "2") (pinfunction "2_2") (pintype "passive"))
      (node (ref "S271") (pin "2") (pinfunction "2_2") (pintype "passive"))
    )
    (net (code "8") (name "/col8") (class "Default")
      (node (ref "S207") (pin "2") (pinfunction "2_2") (pintype "passive"))
      (node (ref "S224") (pin "2") (pinfunction "2_2") (pintype "passive"))
      (node (ref "S241") (pin "2") (pinfunction "2_2") (pintype "passive"))
      (node (ref "S258") (pin "2") (pinfunction "2_2") (pintype "passive"))
      (node (ref "S272") (pin "2") (pinfunction "2_2") (pintype "passive"))
      (node (ref "S283") (pin "1") (pinfunction "1_1") (pintype "passive"))
    )
    (net (code "9") (name "/col9") (class "Default")
      (node (ref "S208") (pin "2") (pinfunction "2_2") (pintype "passive"))
      (node (ref "S225") (pin "2") (pinfunction "2_2") (pintype "passive"))
      (node (ref "S242") (pin "2") (pinfunction "2_2") (pintype "passive"))
      (node (ref "S259") (pin "2") (pinfunction "2_2") (pintype "passive"))
      (node (ref "S273") (pin "2") (pinfunction "2_2") (pintype "passive"))
    )
    (net (code "10") (name "/col10") (class "Default")
      (node (ref "S209") (pin "2") (pinfunction "2_2") (pintype "passive"))
      (node (ref "S226") (pin "2") (pinfunction "2_2") (pintype "passive"))
      (node (ref "S243") (pin "2") (pinfunction "2_2") (pintype "passive"))
      (node (ref "S260") (pin "2") (pinfunction "2_2") (pintype "passive"))
      (node (ref "S274") (pin "2") (pinfunction "2_2") (pintype "passive"))
    )
    (net (code "11") (name "/col11") (class "Default")
      (node (ref "S210") (pin "2") (pinfunction "2_2") (pintype "passive"))
      (node (ref "S227") (pin "2") (pinfunction "2_2") (pintype "passive"))
      (node (ref "S244") (pin "2") (pinfunction "2_2") (pintype "passive"))
      (node (ref "S261") (pin "2") (pinfunction "2_2") (pintype "passive"))
      (node (ref "S275") (pin "2") (pinfunction "2_2") (pintype "passive"))
    )
    (net (code "12") (name "/col12") (class "Default")
      (node (ref "S211") (pin "2") (pinfunction "2_2") (pintype "passive"))
      (node (ref "S228") (pin "2") (pinfunction "2_2") (pintype "passive"))
      (node (ref "S245") (pin "2") (pinfunction "2_2") (pintype "passive"))
      (node (ref "S262") (pin "2") (pinfunction "2_2") (pintype "passive"))
      (node (ref "S276") (pin "2") (pinfunction "2_2") (pintype "passive"))
      (node (ref "S284") (pin "2") (pinfunction "2_2") (pintype "passive"))
    )
    (net (code "13") (name "/col13") (class "Default")
      (node (ref "S212") (pin "2") (pinfunction "2_2") (pintype "passive"))
      (node (ref "S229") (pin "2") (pinfunction "2_2") (pintype "passive"))
      (node (ref "S246") (pin "2") (pinfunction "2_2") (pintype "passive"))
      (node (ref "S263") (pin "2") (pinfunction "2_2") (pintype "passive"))
      (node (ref "S277") (pin "2") (pinfunction "2_2") (pintype "passive"))
    )
    (net (code "14") (name "/col14") (class "Default")
      (node (ref "S213") (pin "2") (pinfunction "2_2") (pintype "passive"))
      (node (ref "S247") (pin "2") (pinfunction "2_2") (pintype "passive"))
      (node (ref "S264") (pin "2") (pinfunction "2_2") (pintype "passive"))
      (node (ref "S286") (pin "2") (pinfunction "2_2") (pintype "passive"))
    )
    (net (code "15") (name "/col15") (class "Default")
      (node (ref "S214") (pin "2") (pinfunction "2_2") (pintype "passive"))
      (node (ref "S231") (pin "2") (pinfunction "2_2") (pintype "passive"))
      (node (ref "S248") (pin "2") (pinfunction "2_2") (pintype "passive"))
      (node (ref "S287") (pin "2") (pinfunction "2_2") (pintype "passive"))
    )
    (net (code "16") (name "/col16") (class "Default")
      (node (ref "S215") (pin "2") (pinfunction "2_2") (pintype "passive"))
      (node (ref "S232") (pin "2") (pinfunction "2_2") (pintype "passive"))
      (node (ref "S249") (pin "2") (pinfunction "2_2") (pintype "passive"))
      (node (ref "S279") (pin "2") (pinfunction "2_2") (pintype "passive"))
      (node (ref "S288") (pin "2") (pinfunction "2_2") (pintype "passive"))
    )
    (net (code "17") (name "/col17") (class "Default")
      (node (ref "S216") (pin "2") (pinfunction "2_2") (pintype "passive"))
      (node (ref "S233") (pin "2") (pinfunction "2_2") (pintype "passive"))
      (node (ref "S250") (pin "2") (pinfunction "2_2") (pintype "passive"))
      (node (ref "S289") (pin "2") (pinfunction "2_2") (pintype "passive"))
    )
    (net (code "18") (name "/row1") (class "Default")
      (node (ref "D201") (pin "2") (pinfunction "K_2") (pintype "passive"))
      (node (ref "D202") (pin "2") (pinfunction "K_2") (pintype "passive"))
      (node (ref "D203") (pin "2") (pinfunction "K_2") (pintype "passive"))
      (node (ref "D204") (pin "2") (pinfunction "K_2") (pintype "passive"))
      (node (ref "D205") (pin "2") (pinfunction "K_2") (pintype "passive"))
      (node (ref "D206") (pin "2") (pinfunction "K_2") (pintype "passive"))
      (node (ref "D207") (pin "2") (pinfunction "K_2") (pintype "passive"))
      (node (ref "D208") (pin "2") (pinfunction "K_2") (pintype "passive"))
      (node (ref "D209") (pin "2") (pinfunction "K_2") (pintype "passive"))
      (node (ref "D210") (pin "2") (pinfunction "K_2") (pintype "passive"))
      (node (ref "D211") (pin "2") (pinfunction "K_2") (pintype "passive"))
      (node (ref "D212") (pin "2") (pinfunction "K_2") (pintype "passive"))
      (node (ref "D213") (pin "2") (pinfunction "K_2") (pintype "passive"))
      (node (ref "D214") (pin "2") (pinfunction "K_2") (pintype "passive"))
      (node (ref "D215") (pin "2") (pinfunction "K_2") (pintype "passive"))
      (node (ref "D216") (pin "2") (pinfunction "K_2") (pintype "passive"))
    )
    (net (code "19") (name "/row2") (class "Default")
      (node (ref "D217") (pin "2") (pinfunction "K_2") (pintype "passive"))
      (node (ref "D218") (pin "2") (pinfunction "K_2") (pintype "passive"))
      (node (ref "D219") (pin "2") (pinfunction "K_2") (pintype "passive"))
      (node (ref "D220") (pin "2") (pinfunction "K_2") (pintype "passive"))
      (node (ref "D221") (pin "2") (pinfunction "K_2") (pintype "passive"))
      (node (ref "D222") (pin "2") (pinfunction "K_2") (pintype "passive"))
      (node (ref "D223") (pin "2") (pinfunction "K_2") (pintype "passive"))
      (node (ref "D224") (pin "2") (pinfunction "K_2") (pintype "passive"))
      (node (ref "D225") (pin "2") (pinfunction "K_2") (pintype "passive"))
      (node (ref "D226") (pin "2") (pinfunction "K_2") (pintype "passive"))
      (node (ref "D227") (pin "2") (pinfunction "K_2") (pintype "passive"))
      (node (ref "D228") (pin "2") (pinfunction "K_2") (pintype "passive"))
      (node (ref "D229") (pin "2") (pinfunction "K_2") (pintype "passive"))
      (node (ref "D231") (pin "2") (pinfunction "K_2") (pintype "passive"))
      (node (ref "D232") (pin "2") (pinfunction "K_2") (pintype "passive"))
      (node (ref "D233") (pin "2") (pinfunction "K_2") (pintype "passive"))
    )
    (net (code "20") (name "/row3") (class "Default")
      (node (ref "D234") (pin "2") (pinfunction "K_2") (pintype "passive"))
      (node (ref "D235") (pin "2") (pinfunction "K_2") (pintype "passive"))
      (node (ref "D236") (pin "2") (pinfunction "K_2") (pintype "passive"))
      (node (ref "D237") (pin "2") (pinfunction "K_2") (pintype "passive"))
      (node (ref "D238") (pin "2") (pinfunction "K_2") (pintype "passive"))
      (node (ref "D239") (pin "2") (pinfunction "K_2") (pintype "passive"))
      (node (ref "D240") (pin "2") (pinfunction "K_2") (pintype "passive"))
      (node (ref "D241") (pin "2") (pinfunction "K_2") (pintype "passive"))
      (node (ref "D242") (pin "2") (pinfunction "K_2") (pintype "passive"))
      (node (ref "D243") (pin "2") (pinfunction "K_2") (pintype "passive"))
      (node (ref "D244") (pin "2") (pinfunction "K_2") (pintype "passive"))
      (node (ref "D245") (pin "2") (pinfunction "K_2") (pintype "passive"))
      (node (ref "D246") (pin "2") (pinfunction "K_2") (pintype "passive"))
      (node (ref "D247") (pin "2") (pinfunction "K_2") (pintype "passive"))
      (node (ref "D248") (pin "2") (pinfunction "K_2") (pintype "passive"))
      (node (ref "D249") (pin "2") (pinfunction "K_2") (pintype "passive"))
      (node (ref "D250") (pin "2") (pinfunction "K_2") (pintype "passive"))
    )
    (net (code "21") (name "/row4") (class "Default")
      (node (ref "D251") (pin "2") (pinfunction "K_2") (pintype "passive"))
      (node (ref "D252") (pin "2") (pinfunction "K_2") (pintype "passive"))
      (node (ref "D253") (pin "2") (pinfunction "K_2") (pintype "passive"))
      (node (ref "D254") (pin "2") (pinfunction "K_2") (pintype "passive"))
      (node (ref "D255") (pin "2") (pinfunction "K_2") (pintype "passive"))
      (node (ref "D256") (pin "2") (pinfunction "K_2") (pintype "passive"))
      (node (ref "D257") (pin "2") (pinfunction "K_2") (pintype "passive"))
      (node (ref "D258") (pin "2") (pinfunction "K_2") (pintype "passive"))
      (node (ref "D259") (pin "2") (pinfunction "K_2") (pintype "passive"))
      (node (ref "D260") (pin "2") (pinfunction "K_2") (pintype "passive"))
      (node (ref "D261") (pin "2") (pinfunction "K_2") (pintype "passive"))
      (node (ref "D262") (pin "2") (pinfunction "K_2") (pintype "passive"))
      (node (ref "D263") (pin "2") (pinfunction "K_2") (pintype "passive"))
      (node (ref "D264") (pin "2") (pinfunction "K_2") (pintype "passive"))
    )
    (net (code "22") (name "/row5") (class "Default")
      (node (ref "D265") (pin "2") (pinfunction "K_2") (pintype "passive"))
      (node (ref "D267") (pin "2") (pinfunction "K_2") (pintype "passive"))
      (node (ref "D268") (pin "2") (pinfunction "K_2") (pintype "passive"))
      (node (ref "D269") (pin "2") (pinfunction "K_2") (pintype "passive"))
      (node (ref "D270") (pin "2") (pinfunction "K_2") (pintype "passive"))
      (node (ref "D271") (pin "2") (pinfunction "K_2") (pintype "passive"))
      (node (ref "D272") (pin "2") (pinfunction "K_2") (pintype "passive"))
      (node (ref "D273") (pin "2") (pinfunction "K_2") (pintype "passive"))
      (node (ref "D274") (pin "2") (pinfunction "K_2") (pintype "passive"))
      (node (ref "D275") (pin "2") (pinfunction "K_2") (pintype "passive"))
      (node (ref "D276") (pin "2") (pinfunction "K_2") (pintype "passive"))
      (node (ref "D277") (pin "2") (pinfunction "K_2") (pintype "passive"))
      (node (ref "D279") (pin "2") (pinfunction "K_2") (pintype "passive"))
    )
    (net (code "23") (name "/row6") (class "Default")
      (node (ref "D280") (pin "2") (pinfunction "K_2") (pintype "passive"))
      (node (ref "D282") (pin "2") (pinfunction "K_2") (pintype "passive"))
      (node (ref "D283") (pin "2") (pinfunction "K_2") (pintype "passive"))
      (node (ref "D284") (pin "2") (pinfunction "K_2") (pintype "passive"))
      (node (ref "D286") (pin "2") (pinfunction "K_2") (pintype "passive"))
      (node (ref "D287") (pin "2") (pinfunction "K_2") (pintype "passive"))
      (node (ref "D288") (pin "2") (pinfunction "K_2") (pintype "passive"))
      (node (ref "D289") (pin "2") (pinfunction "K_2") (pintype "passive"))
    )
    (net (code "24") (name "Net-(D201-A)") (class "Default")
      (node (ref "D201") (pin "1") (pinfunction "A_1") (pintype "passive"))
      (node (ref "S201") (pin "1") (pinfunction "1_1") (pintype "passive"))
    )
    (net (code "25") (name "Net-(D202-A)") (class "Default")
      (node (ref "D202") (pin "1") (pinfunction "A_1") (pintype "passive"))
      (node (ref "S202") (pin "1") (pinfunction "1_1") (pintype "passive"))
    )
    (net (code "26") (name "Net-(D203-A)") (class "Default")
      (node (ref "D203") (pin "1") (pinfunction "A_1") (pintype "passive"))
      (node (ref "S203") (pin "1") (pinfunction "1_1") (pintype "passive"))
    )
    (net (code "27") (name "Net-(D204-A)") (class "Default")
      (node (ref "D204") (pin "1") (pinfunction "A_1") (pintype "passive"))
      (node (ref "S204") (pin "1") (pinfunction "1_1") (pintype "passive"))
    )
    (net (code "28") (name "Net-(D205-A)") (class "Default")
      (node (ref "D205") (pin "1") (pinfunction "A_1") (pintype "passive"))
      (node (ref "S205") (pin "1") (pinfunction "1_1") (pintype "passive"))
    )
    (net (code "29") (name "Net-(D206-A)") (class "Default")
      (node (ref "D206") (pin "1") (pinfunction "A_1") (pintype "passive"))
      (node (ref "S206") (pin "1") (pinfunction "1_1") (pintype "passive"))
    )
    (net (code "30") (name "Net-(D207-A)") (class "Default")
      (node (ref "D207") (pin "1") (pinfunction "A_1") (pintype "passive"))
      (node (ref "S207") (pin "1") (pinfunction "1_1") (pintype "passive"))
    )
    (net (code "31") (name "Net-(D208-A)") (class "Default")
      (node (ref "D208") (pin "1") (pinfunction "A_1") (pintype "passive"))
      (node (ref "S208") (pin "1") (pinfunction "1_1") (pintype "passive"))
    )
    (net (code "32") (name "Net-(D209-A)") (class "Default")
      (node (ref "D209") (pin "1") (pinfunction "A_1") (pintype "passive"))
      (node (ref "S209") (pin "1") (pinfunction "1_1") (pintype "passive"))
    )
    (net (code "33") (name "Net-(D210-A)") (class "Default")
      (node (ref "D210") (pin "1") (pinfunction "A_1") (pintype "passive"))
      (node (ref "S210") (pin "1") (pinfunction "1_1") (pintype "passive"))
    )
    (net (code "34") (name "Net-(D211-A)") (class "Default")
      (node (ref "D211") (pin "1") (pinfunction "A_1") (pintype "passive"))
      (node (ref "S211") (pin "1") (pinfunction "1_1") (pintype "passive"))
    )
    (net (code "35") (name "Net-(D212-A)") (class "Default")
      (node (ref "D212") (pin "1") (pinfunction "A_1") (pintype "passive"))
      (node (ref "S212") (pin "1") (pinfunction "1_1") (pintype "passive"))
    )
    (net (code "36") (name "Net-(D213-A)") (class "Default")
      (node (ref "D213") (pin "1") (pinfunction "A_1") (pintype "passive"))
      (node (ref "S213") (pin "1") (pinfunction "1_1") (pintype "passive"))
    )
    (net (code "37") (name "Net-(D214-A)") (class "Default")
      (node (ref "D214") (pin "1") (pinfunction "A_1") (pintype "passive"))
      (node (ref "S214") (pin "1") (pinfunction "1_1") (pintype "passive"))
    )
    (net (code "38") (name "Net-(D215-A)") (class "Default")
      (node (ref "D215") (pin "1") (pinfunction "A_1") (pintype "passive"))
      (node (ref "S215") (pin "1") (pinfunction "1_1") (pintype "passive"))
    )
    (net (code "39") (name "Net-(D216-A)") (class "Default")
      (node (ref "D216") (pin "1") (pinfunction "A_1") (pintype "passive"))
      (node (ref "S216") (pin "1") (pinfunction "1_1") (pintype "passive"))
    )
    (net (code "40") (name "Net-(D217-A)") (class "Default")
      (node (ref "D217") (pin "1") (pinfunction "A_1") (pintype "passive"))
      (node (ref "S217") (pin "1") (pinfunction "1_1") (pintype "passive"))
    )
    (net (code "41") (name "Net-(D218-A)") (class "Default")
      (node (ref "D218") (pin "1") (pinfunction "A_1") (pintype "passive"))
      (node (ref "S218") (pin "1") (pinfunction "1_1") (pintype "passive"))
    )
    (net (code "42") (name "Net-(D219-A)") (class "Default")
      (node (ref "D219") (pin "1") (pinfunction "A_1") (pintype "passive"))
      (node (ref "S219") (pin "1") (pinfunction "1_1") (pintype "passive"))
    )
    (net (code "43") (name "Net-(D220-A)") (class "Default")
      (node (ref "D220") (pin "1") (pinfunction "A_1") (pintype "passive"))
      (node (ref "S220") (pin "1") (pinfunction "1_1") (pintype "passive"))
    )
    (net (code "44") (name "Net-(D221-A)") (class "Default")
      (node (ref "D221") (pin "1") (pinfunction "A_1") (pintype "passive"))
      (node (ref "S221") (pin "1") (pinfunction "1_1") (pintype "passive"))
    )
    (net (code "45") (name "Net-(D222-A)") (class "Default")
      (node (ref "D222") (pin "1") (pinfunction "A_1") (pintype "passive"))
      (node (ref "S222") (pin "1") (pinfunction "1_1") (pintype "passive"))
    )
    (net (code "46") (name "Net-(D223-A)") (class "Default")
      (node (ref "D223") (pin "1") (pinfunction "A_1") (pintype "passive"))
      (node (ref "S223") (pin "1") (pinfunction "1_1") (pintype "passive"))
    )
    (net (code "47") (name "Net-(D224-A)") (class "Default")
      (node (ref "D224") (pin "1") (pinfunction "A_1") (pintype "passive"))
      (node (ref "S224") (pin "1") (pinfunction "1_1") (pintype "passive"))
    )
    (net (code "48") (name "Net-(D225-A)") (class "Default")
      (node (ref "D225") (pin "1") (pinfunction "A_1") (pintype "passive"))
      (node (ref "S225") (pin "1") (pinfunction "1_1") (pintype "passive"))
    )
    (net (code "49") (name "Net-(D226-A)") (class "Default")
      (node (ref "D226") (pin "1") (pinfunction "A_1") (pintype "passive"))
      (node (ref "S226") (pin "1") (pinfunction "1_1") (pintype "passive"))
    )
    (net (code "50") (name "Net-(D227-A)") (class "Default")
      (node (ref "D227") (pin "1") (pinfunction "A_1") (pintype "passive"))
      (node (ref "S227") (pin "1") (pinfunction "1_1") (pintype "passive"))
    )
    (net (code "51") (name "Net-(D228-A)") (class "Default")
      (node (ref "D228") (pin "1") (pinfunction "A_1") (pintype "passive"))
      (node (ref "S228") (pin "1") (pinfunction "1_1") (pintype "passive"))
    )
    (net (code "52") (name "Net-(D229-A)") (class "Default")
      (node (ref "D229") (pin "1") (pinfunction "A_1") (pintype "passive"))
      (node (ref "S229") (pin "1") (pinfunction "1_1") (pintype "passive"))
    )
    (net (code "53") (name "Net-(D231-A)") (class "Default")
      (node (ref "D231") (pin "1") (pinfunction "A_1") (pintype "passive"))
      (node (ref "S231") (pin "1") (pinfunction "1_1") (pintype "passive"))
    )
    (net (code "54") (name "Net-(D232-A)") (class "Default")
      (node (ref "D232") (pin "1") (pinfunction "A_1") (pintype "passive"))
      (node (ref "S232") (pin "1") (pinfunction "1_1") (pintype "passive"))
    )
    (net (code "55") (name "Net-(D233-A)") (class "Default")
      (node (ref "D233") (pin "1") (pinfunction "A_1") (pintype "passive"))
      (node (ref "S233") (pin "1") (pinfunction "1_1") (pintype "passive"))
    )
    (net (code "56") (name "Net-(D234-A)") (class "Default")
      (node (ref "D234") (pin "1") (pinfunction "A_1") (pintype "passive"))
      (node (ref "S234") (pin "1") (pinfunction "1_1") (pintype "passive"))
    )
    (net (code "57") (name "Net-(D235-A)") (class "Default")
      (node (ref "D235") (pin "1") (pinfunction "A_1") (pintype "passive"))
      (node (ref "S235") (pin "1") (pinfunction "1_1") (pintype "passive"))
    )
    (net (code "58") (name "Net-(D236-A)") (class "Default")
      (node (ref "D236") (pin "1") (pinfunction "A_1") (pintype "passive"))
      (node (ref "S236") (pin "1") (pinfunction "1_1") (pintype "passive"))
    )
    (net (code "59") (name "Net-(D237-A)") (class "Default")
      (node (ref "D237") (pin "1") (pinfunction "A_1") (pintype "passive"))
      (node (ref "S237") (pin "1") (pinfunction "1_1") (pintype "passive"))
    )
    (net (code "60") (name "Net-(D238-A)") (class "Default")
      (node (ref "D238") (pin "1") (pinfunction "A_1") (pintype "passive"))
      (node (ref "S238") (pin "1") (pinfunction "1_1") (pintype "passive"))
    )
    (net (code "61") (name "Net-(D239-A)") (class "Default")
      (node (ref "D239") (pin "1") (pinfunction "A_1") (pintype "passive"))
      (node (ref "S239") (pin "1") (pinfunction "1_1") (pintype "passive"))
    )
    (net (code "62") (name "Net-(D240-A)") (class "Default")
      (node (ref "D240") (pin "1") (pinfunction "A_1") (pintype "passive"))
      (node (ref "S240") (pin "1") (pinfunction "1_1") (pintype "passive"))
    )
    (net (code "63") (name "Net-(D241-A)") (class "Default")
      (node (ref "D241") (pin "1") (pinfunction "A_1") (pintype "passive"))
      (node (ref "S241") (pin "1") (pinfunction "1_1") (pintype "passive"))
    )
    (net (code "64") (name "Net-(D242-A)") (class "Default")
      (node (ref "D242") (pin "1") (pinfunction "A_1") (pintype "passive"))
      (node (ref "S242") (pin "1") (pinfunction "1_1") (pintype "passive"))
    )
    (net (code "65") (name "Net-(D243-A)") (class "Default")
      (node (ref "D243") (pin "1") (pinfunction "A_1") (pintype "passive"))
      (node (ref "S243") (pin "1") (pinfunction "1_1") (pintype "passive"))
    )
    (net (code "66") (name "Net-(D244-A)") (class "Default")
      (node (ref "D244") (pin "1") (pinfunction "A_1") (pintype "passive"))
      (node (ref "S244") (pin "1") (pinfunction "1_1") (pintype "passive"))
    )
    (net (code "67") (name "Net-(D245-A)") (class "Default")
      (node (ref "D245") (pin "1") (pinfunction "A_1") (pintype "passive"))
      (node (ref "S245") (pin "1") (pinfunction "1_1") (pintype "passive"))
    )
    (net (code "68") (name "Net-(D246-A)") (class "Default")
      (node (ref "D246") (pin "1") (pinfunction "A_1") (pintype "passive"))
      (node (ref "S246") (pin "1") (pinfunction "1_1") (pintype "passive"))
    )
    (net (code "69") (name "Net-(D247-A)") (class "Default")
      (node (ref "D247") (pin "1") (pinfunction "A_1") (pintype "passive"))
      (node (ref "S247") (pin "1") (pinfunction "1_1") (pintype "passive"))
    )
    (net (code "70") (name "Net-(D248-A)") (class "Default")
      (node (ref "D248") (pin "1") (pinfunction "A_1") (pintype "passive"))
      (node (ref "S248") (pin "1") (pinfunction "1_1") (pintype "passive"))
    )
    (net (code "71") (name "Net-(D249-A)") (class "Default")
      (node (ref "D249") (pin "1") (pinfunction "A_1") (pintype "passive"))
      (node (ref "S249") (pin "1") (pinfunction "1_1") (pintype "passive"))
    )
    (net (code "72") (name "Net-(D250-A)") (class "Default")
      (node (ref "D250") (pin "1") (pinfunction "A_1") (pintype "passive"))
      (node (ref "S250") (pin "1") (pinfunction "1_1") (pintype "passive"))
    )
    (net (code "73") (name "Net-(D251-A)") (class "Default")
      (node (ref "D251") (pin "1") (pinfunction "A_1") (pintype "passive"))
      (node (ref "S251") (pin "1") (pinfunction "1_1") (pintype "passive"))
    )
    (net (code "74") (name "Net-(D252-A)") (class "Default")
      (node (ref "D252") (pin "1") (pinfunction "A_1") (pintype "passive"))
      (node (ref "S252") (pin "1") (pinfunction "1_1") (pintype "passive"))
    )
    (net (code "75") (name "Net-(D253-A)") (class "Default")
      (node (ref "D253") (pin "1") (pinfunction "A_1") (pintype "passive"))
      (node (ref "S253") (pin "1") (pinfunction "1_1") (pintype "passive"))
    )
    (net (code "76") (name "Net-(D254-A)") (class "Default")
      (node (ref "D254") (pin "1") (pinfunction "A_1") (pintype "passive"))
      (node (ref "S254") (pin "1") (pinfunction "1_1") (pintype "passive"))
    )
    (net (code "77") (name "Net-(D255-A)") (class "Default")
      (node (ref "D255") (pin "1") (pinfunction "A_1") (pintype "passive"))
      (node (ref "S255") (pin "1") (pinfunction "1_1") (pintype "passive"))
    )
    (net (code "78") (name "Net-(D256-A)") (class "Default")
      (node (ref "D256") (pin "1") (pinfunction "A_1") (pintype "passive"))
      (node (ref "S256") (pin "1") (pinfunction "1_1") (pintype "passive"))
    )
    (net (code "79") (name "Net-(D257-A)") (class "Default")
      (node (ref "D257") (pin "1") (pinfunction "A_1") (pintype "passive"))
      (node (ref "S257") (pin "1") (pinfunction "1_1") (pintype "passive"))
    )
    (net (code "80") (name "Net-(D258-A)") (class "Default")
      (node (ref "D258") (pin "1") (pinfunction "A_1") (pintype "passive"))
      (node (ref "S258") (pin "1") (pinfunction "1_1") (pintype "passive"))
    )
    (net (code "81") (name "Net-(D259-A)") (class "Default")
      (node (ref "D259") (pin "1") (pinfunction "A_1") (pintype "passive"))
      (node (ref "S259") (pin "1") (pinfunction "1_1") (pintype "passive"))
    )
    (net (code "82") (name "Net-(D260-A)") (class "Default")
      (node (ref "D260") (pin "1") (pinfunction "A_1") (pintype "passive"))
      (node (ref "S260") (pin "1") (pinfunction "1_1") (pintype "passive"))
    )
    (net (code "83") (name "Net-(D261-A)") (class "Default")
      (node (ref "D261") (pin "1") (pinfunction "A_1") (pintype "passive"))
      (node (ref "S261") (pin "1") (pinfunction "1_1") (pintype "passive"))
    )
    (net (code "84") (name "Net-(D262-A)") (class "Default")
      (node (ref "D262") (pin "1") (pinfunction "A_1") (pintype "passive"))
      (node (ref "S262") (pin "1") (pinfunction "1_1") (pintype "passive"))
    )
    (net (code "85") (name "Net-(D263-A)") (class "Default")
      (node (ref "D263") (pin "1") (pinfunction "A_1") (pintype "passive"))
      (node (ref "S263") (pin "1") (pinfunction "1_1") (pintype "passive"))
    )
    (net (code "86") (name "Net-(D264-A)") (class "Default")
      (node (ref "D264") (pin "1") (pinfunction "A_1") (pintype "passive"))
      (node (ref "S264") (pin "1") (pinfunction "1_1") (pintype "passive"))
    )
    (net (code "87") (name "Net-(D265-A)") (class "Default")
      (node (ref "D265") (pin "1") (pinfunction "A_1") (pintype "passive"))
      (node (ref "S265") (pin "1") (pinfunction "1_1") (pintype "passive"))
    )
    (net (code "88") (name "Net-(D267-A)") (class "Default")
      (node (ref "D267") (pin "1") (pinfunction "A_1") (pintype "passive"))
      (node (ref "S267") (pin "1") (pinfunction "1_1") (pintype "passive"))
    )
    (net (code "89") (name "Net-(D268-A)") (class "Default")
      (node (ref "D268") (pin "1") (pinfunction "A_1") (pintype "passive"))
      (node (ref "S268") (pin "1") (pinfunction "1_1") (pintype "passive"))
    )
    (net (code "90") (name "Net-(D269-A)") (class "Default")
      (node (ref "D269") (pin "1") (pinfunction "A_1") (pintype "passive"))
      (node (ref "S269") (pin "1") (pinfunction "1_1") (pintype "passive"))
    )
    (net (code "91") (name "Net-(D270-A)") (class "Default")
      (node (ref "D270") (pin "1") (pinfunction "A_1") (pintype "passive"))
      (node (ref "S270") (pin "1") (pinfunction "1_1") (pintype "passive"))
    )
    (net (code "92") (name "Net-(D271-A)") (class "Default")
      (node (ref "D271") (pin "1") (pinfunction "A_1") (pintype "passive"))
      (node (ref "S271") (pin "1") (pinfunction "1_1") (pintype "passive"))
    )
    (net (code "93") (name "Net-(D272-A)") (class "Default")
      (node (ref "D272") (pin "1") (pinfunction "A_1") (pintype "passive"))
      (node (ref "S272") (pin "1") (pinfunction "1_1") (pintype "passive"))
    )
    (net (code "94") (name "Net-(D273-A)") (class "Default")
      (node (ref "D273") (pin "1") (pinfunction "A_1") (pintype "passive"))
      (node (ref "S273") (pin "1") (pinfunction "1_1") (pintype "passive"))
    )
    (net (code "95") (name "Net-(D274-A)") (class "Default")
      (node (ref "D274") (pin "1") (pinfunction "A_1") (pintype "passive"))
      (node (ref "S274") (pin "1") (pinfunction "1_1") (pintype "passive"))
    )
    (net (code "96") (name "Net-(D275-A)") (class "Default")
      (node (ref "D275") (pin "1") (pinfunction "A_1") (pintype "passive"))
      (node (ref "S275") (pin "1") (pinfunction "1_1") (pintype "passive"))
    )
    (net (code "97") (name "Net-(D276-A)") (class "Default")
      (node (ref "D276") (pin "1") (pinfunction "A_1") (pintype "passive"))
      (node (ref "S276") (pin "1") (pinfunction "1_1") (pintype "passive"))
    )
    (net (code "98") (name "Net-(D277-A)") (class "Default")
      (node (ref "D277") (pin "1") (pinfunction "A_1") (pintype "passive"))
      (node (ref "S277") (pin "1") (pinfunction "1_1") (pintype "passive"))
    )
    (net (code "99") (name "Net-(D279-A)") (class "Default")
      (node (ref "D279") (pin "1") (pinfunction "A_1") (pintype "passive"))
      (node (ref "S279") (pin "1") (pinfunction "1_1") (pintype "passive"))
    )
    (net (code "100") (name "Net-(D280-A)") (class "Default")
      (node (ref "D280") (pin "1") (pinfunction "A_1") (pintype "passive"))
      (node (ref "S280") (pin "1") (pinfunction "1_1") (pintype "passive"))
    )
    (net (code "101") (name "Net-(D282-A)") (class "Default")
      (node (ref "D282") (pin "1") (pinfunction "A_1") (pintype "passive"))
      (node (ref "S282") (pin "1") (pinfunction "1_1") (pintype "passive"))
    )
    (net (code "102") (name "Net-(D283-A)") (class "Default")
      (node (ref "D283") (pin "1") (pinfunction "A_1") (pintype "passive"))
      (node (ref "S283") (pin "2") (pinfunction "2_2") (pintype "passive"))
    )
    (net (code "103") (name "Net-(D284-A)") (class "Default")
      (node (ref "D284") (pin "1") (pinfunction "A_1") (pintype "passive"))
      (node (ref "S284") (pin "1") (pinfunction "1_1") (pintype "passive"))
    )
    (net (code "104") (name "Net-(D286-A)") (class "Default")
      (node (ref "D286") (pin "1") (pinfunction "A_1") (pintype "passive"))
      (node (ref "S286") (pin "1") (pinfunction "1_1") (pintype "passive"))
    )
    (net (code "105") (name "Net-(D287-A)") (class "Default")
      (node (ref "D287") (pin "1") (pinfunction "A_1") (pintype "passive"))
      (node (ref "S287") (pin "1") (pinfunction "1_1") (pintype "passive"))
    )
    (net (code "106") (name "Net-(D288-A)") (class "Default")
      (node (ref "D288") (pin "1") (pinfunction "A_1") (pintype "passive"))
      (node (ref "S288") (pin "1") (pinfunction "1_1") (pintype "passive"))
    )
    (net (code "107") (name "Net-(D289-A)") (class "Default")
      (node (ref "D289") (pin "1") (pinfunction "A_1") (pintype "passive"))
      (node (ref "S289") (pin "1") (pinfunction "1_1") (pintype "passive"))
    )
    (net (code "108") (name "unconnected-(STAB1-Pad1)") (class "Default")
      (node (ref "STAB1") (pin "1") (pinfunction "1_1") (pintype "passive"))
    )
    (net (code "109") (name "unconnected-(STAB2-Pad1)") (class "Default")
      (node (ref "STAB2") (pin "1") (pinfunction "1_1") (pintype "passive"))
    )
    (net (code "110") (name "unconnected-(STAB3-Pad1)") (class "Default")
      (node (ref "STAB3") (pin "1") (pinfunction "1_1") (pintype "passive"))
    )
    (net (code "111") (name "unconnected-(STAB4-Pad1)") (class "Default")
      (node (ref "STAB4") (pin "1") (pinfunction "1_1") (pintype "passive"))
    )
    (net (code "112") (name "unconnected-(STAB5-Pad1)") (class "Default")
      (node (ref "STAB5") (pin "1") (pinfunction "1_1") (pintype "passive"))
    )
  )
)
